# sensors.net
KiCad netlist of a schematic drawn in EAGLE
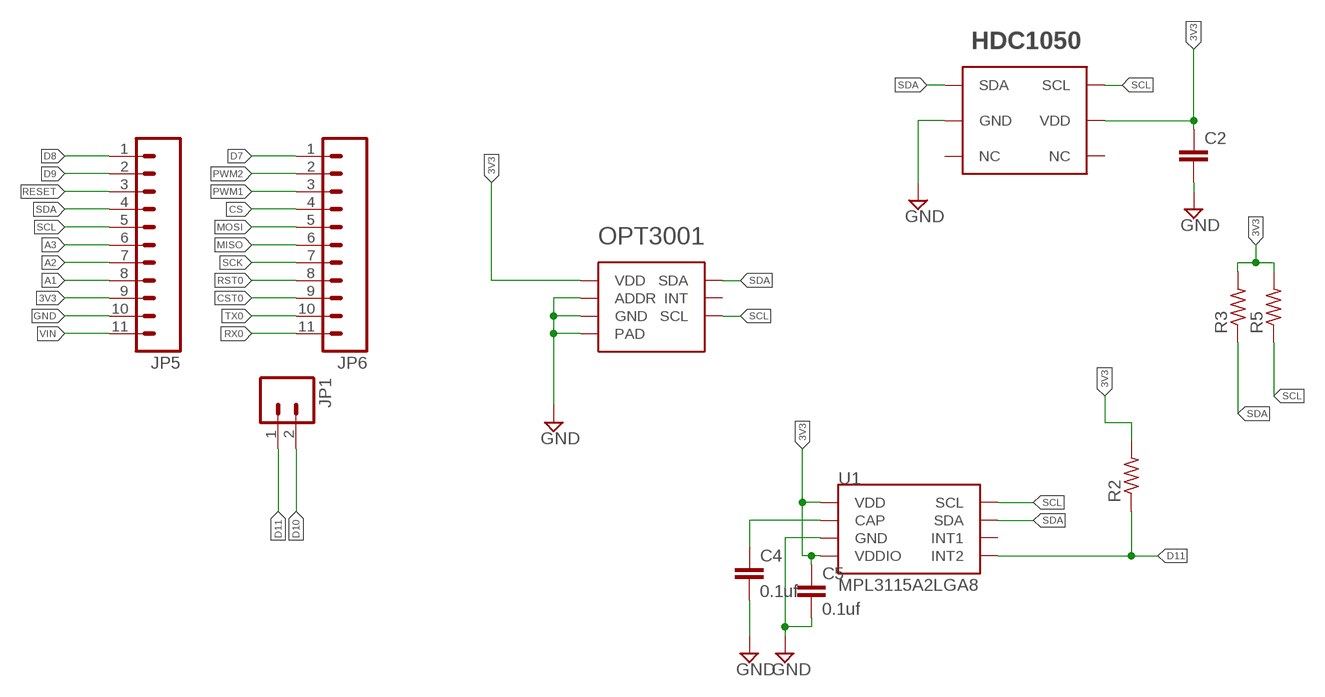
[diagram p0: schematic, sheet 1]

(export (version "E")
  (design (tool "Eeschema 10.0.6"))
  (components
    (comp (ref "C2")
      (value "C-EUC0805")
      (footprint "eagle-import:C0805")
      (libsource (lib "eagle-import") (part "C-EUC0805"))
    )
    (comp (ref "C4")
      (value "0.1uf")
      (footprint "eagle-import:C0805")
      (libsource (lib "eagle-import") (part "C-EUC0805"))
    )
    (comp (ref "C5")
      (value "0.1uf")
      (footprint "eagle-import:C0805")
      (libsource (lib "eagle-import") (part "C-EUC0805"))
    )
    (comp (ref "HDC1050")
      (value "HDC1050")
      (footprint "eagle-import:PWSON-6")
      (libsource (lib "eagle-import") (part "HDC1050"))
    )
    (comp (ref "JP1")
      (value "M02PTH")
      (footprint "eagle-import:1X02")
      (libsource (lib "eagle-import") (part "M02PTH"))
    )
    (comp (ref "JP5")
      (value "M11PTH")
      (footprint "eagle-import:1X11")
      (libsource (lib "eagle-import") (part "M11PTH"))
    )
    (comp (ref "JP6")
      (value "M11PTH")
      (footprint "eagle-import:1X11")
      (libsource (lib "eagle-import") (part "M11PTH"))
    )
    (comp (ref "OPT3001")
      (value "OPT3001")
      (footprint "eagle-import:OPT3001")
      (libsource (lib "eagle-import") (part "OPT3001"))
    )
    (comp (ref "R2")
      (value "R-US_0204/5")
      (footprint "eagle-import:0204_5")
      (libsource (lib "eagle-import") (part "R-US_0204/5"))
    )
    (comp (ref "R3")
      (value "R-US_0204/5")
      (footprint "eagle-import:0204_5")
      (libsource (lib "eagle-import") (part "R-US_0204/5"))
    )
    (comp (ref "R5")
      (value "R-US_0204/5")
      (footprint "eagle-import:0204_5")
      (libsource (lib "eagle-import") (part "R-US_0204/5"))
    )
    (comp (ref "U1")
      (value "MPL3115A2LGA8")
      (footprint "eagle-import:LGA8")
      (libsource (lib "eagle-import") (part "MPL3115A2LGA8"))
    )
  )
  (nets
    (net (code "1") (name "3V3") (class "Default")
      (node (ref "C2") (pin "1") (pinfunction "1_1") (pintype "passive"))
      (node (ref "C5") (pin "1") (pinfunction "1_1") (pintype "passive"))
      (node (ref "HDC1050") (pin "P$5") (pinfunction "VDD_P$5") (pintype "power_in"))
      (node (ref "JP5") (pin "9") (pinfunction "9_9") (pintype "passive"))
      (node (ref "OPT3001") (pin "P$1") (pinfunction "VDD_P$1") (pintype "power_in"))
      (node (ref "R2") (pin "2") (pinfunction "2_2") (pintype "passive"))
      (node (ref "R3") (pin "2") (pinfunction "2_2") (pintype "passive"))
      (node (ref "R5") (pin "2") (pinfunction "2_2") (pintype "passive"))
      (node (ref "U1") (pin "1") (pinfunction "VDD_1") (pintype "power_in"))
      (node (ref "U1") (pin "4") (pinfunction "VDDIO_4") (pintype "power_in"))
    )
    (net (code "2") (name "A1") (class "Default")
      (node (ref "JP5") (pin "8") (pinfunction "8_8") (pintype "passive"))
    )
    (net (code "3") (name "A2") (class "Default")
      (node (ref "JP5") (pin "7") (pinfunction "7_7") (pintype "passive"))
    )
    (net (code "4") (name "A3") (class "Default")
      (node (ref "JP5") (pin "6") (pinfunction "6_6") (pintype "passive"))
    )
    (net (code "5") (name "CS") (class "Default")
      (node (ref "JP6") (pin "4") (pinfunction "4_4") (pintype "passive"))
    )
    (net (code "6") (name "CST0") (class "Default")
      (node (ref "JP6") (pin "9") (pinfunction "9_9") (pintype "passive"))
    )
    (net (code "7") (name "D7") (class "Default")
      (node (ref "JP6") (pin "1") (pinfunction "1_1") (pintype "passive"))
    )
    (net (code "8") (name "D8") (class "Default")
      (node (ref "JP5") (pin "1") (pinfunction "1_1") (pintype "passive"))
    )
    (net (code "9") (name "D9") (class "Default")
      (node (ref "JP5") (pin "2") (pinfunction "2_2") (pintype "passive"))
    )
    (net (code "10") (name "D10") (class "Default")
      (node (ref "JP1") (pin "2") (pinfunction "2_2") (pintype "passive"))
    )
    (net (code "11") (name "D11") (class "Default")
      (node (ref "JP1") (pin "1") (pinfunction "1_1") (pintype "passive"))
      (node (ref "R2") (pin "1") (pinfunction "1_1") (pintype "passive"))
      (node (ref "U1") (pin "5") (pinfunction "INT2_5") (pintype "output"))
    )
    (net (code "12") (name "GND") (class "Default")
      (node (ref "C2") (pin "2") (pinfunction "2_2") (pintype "passive"))
      (node (ref "C4") (pin "2") (pinfunction "2_2") (pintype "passive"))
      (node (ref "C5") (pin "2") (pinfunction "2_2") (pintype "passive"))
      (node (ref "HDC1050") (pin "P$2") (pinfunction "GND_P$2") (pintype "power_in"))
      (node (ref "JP5") (pin "10") (pinfunction "10_10") (pintype "passive"))
      (node (ref "OPT3001") (pin "P$2") (pinfunction "ADDR_P$2") (pintype "input"))
      (node (ref "OPT3001") (pin "P$3") (pinfunction "GND_P$3") (pintype "power_in"))
      (node (ref "OPT3001") (pin "P$7") (pinfunction "PAD_P$7") (pintype "power_in"))
      (node (ref "U1") (pin "3") (pinfunction "GND_3") (pintype "power_in"))
    )
    (net (code "13") (name "MISO") (class "Default")
      (node (ref "JP6") (pin "6") (pinfunction "6_6") (pintype "passive"))
    )
    (net (code "14") (name "MOSI") (class "Default")
      (node (ref "JP6") (pin "5") (pinfunction "5_5") (pintype "passive"))
    )
    (net (code "15") (name "Net-(U1-CAP)") (class "Default")
      (node (ref "C4") (pin "1") (pinfunction "1_1") (pintype "passive"))
      (node (ref "U1") (pin "2") (pinfunction "CAP_2") (pintype "power_in"))
    )
    (net (code "16") (name "PWM1") (class "Default")
      (node (ref "JP6") (pin "3") (pinfunction "3_3") (pintype "passive"))
    )
    (net (code "17") (name "PWM2") (class "Default")
      (node (ref "JP6") (pin "2") (pinfunction "2_2") (pintype "passive"))
    )
    (net (code "18") (name "RESET") (class "Default")
      (node (ref "JP5") (pin "3") (pinfunction "3_3") (pintype "passive"))
    )
    (net (code "19") (name "RST0") (class "Default")
      (node (ref "JP6") (pin "8") (pinfunction "8_8") (pintype "passive"))
    )
    (net (code "20") (name "RX0") (class "Default")
      (node (ref "JP6") (pin "11") (pinfunction "11_11") (pintype "passive"))
    )
    (net (code "21") (name "SCK") (class "Default")
      (node (ref "JP6") (pin "7") (pinfunction "7_7") (pintype "passive"))
    )
    (net (code "22") (name "SCL") (class "Default")
      (node (ref "HDC1050") (pin "P$6") (pinfunction "SCL_P$6") (pintype "bidirectional"))
      (node (ref "JP5") (pin "5") (pinfunction "5_5") (pintype "passive"))
      (node (ref "OPT3001") (pin "P$4") (pinfunction "SCL_P$4") (pintype "input"))
      (node (ref "R5") (pin "1") (pinfunction "1_1") (pintype "passive"))
      (node (ref "U1") (pin "8") (pinfunction "SCL_8") (pintype "bidirectional"))
    )
    (net (code "23") (name "SDA") (class "Default")
      (node (ref "HDC1050") (pin "P$1") (pinfunction "SDA_P$1") (pintype "bidirectional"))
      (node (ref "JP5") (pin "4") (pinfunction "4_4") (pintype "passive"))
      (node (ref "OPT3001") (pin "P$6") (pinfunction "SDA_P$6") (pintype "bidirectional"))
      (node (ref "R3") (pin "1") (pinfunction "1_1") (pintype "passive"))
      (node (ref "U1") (pin "7") (pinfunction "SDA_7") (pintype "bidirectional"))
    )
    (net (code "24") (name "TX0") (class "Default")
      (node (ref "JP6") (pin "10") (pinfunction "10_10") (pintype "passive"))
    )
    (net (code "25") (name "VIN") (class "Default")
      (node (ref "JP5") (pin "11") (pinfunction "11_11") (pintype "passive"))
    )
    (net (code "26") (name "unconnected-(HDC1050-NC-PadP$3)") (class "Default")
      (node (ref "HDC1050") (pin "P$3") (pinfunction "NC_P$3") (pintype "no_connect"))
    )
    (net (code "27") (name "unconnected-(HDC1050-NC-PadP$4)") (class "Default")
      (node (ref "HDC1050") (pin "P$4") (pinfunction "NC_P$4") (pintype "no_connect"))
    )
    (net (code "28") (name "unconnected-(OPT3001-INT-PadP$5)") (class "Default")
      (node (ref "OPT3001") (pin "P$5") (pinfunction "INT_P$5") (pintype "output"))
    )
    (net (code "29") (name "unconnected-(U1-INT1-Pad6)") (class "Default")
      (node (ref "U1") (pin "6") (pinfunction "INT1_6") (pintype "output"))
    )
  )
)
